# Humanoid_Robotic_Hand.net
KiCad netlist of a schematic drawn in Altium Designer
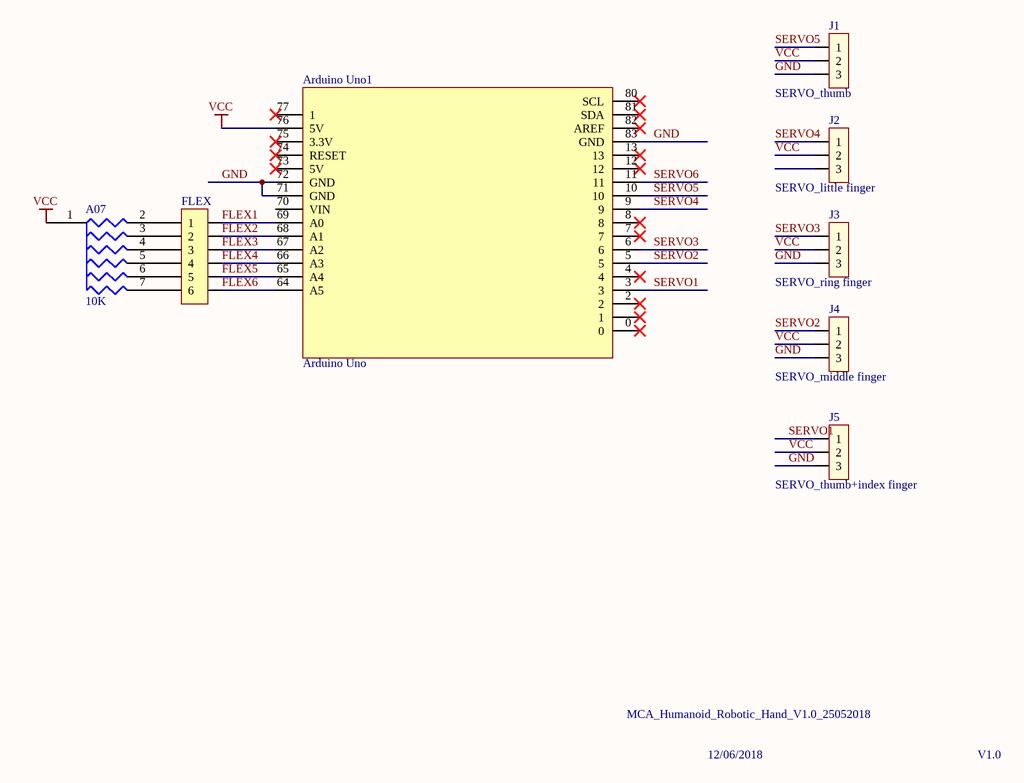
[diagram p0: Humanoid_Robotic_Hand.SchDoc]

(export (version "E")
  (design (tool "Eeschema 10.0.6"))
  (components
    (comp (ref "A07")
      (value "10K")
      (footprint "RES PACK A07")
      (libsource (lib "MH_Thu Vien Du An") (part "Res Pack A07"))
    )
    (comp (ref "Arduino Uno1")
      (value "Arduino Uno")
      (footprint "Arduino Uno")
      (fields (field (name "PUBLISHER") "Altium Limited"))
      (libsource (lib "NamTEch_Lib") (part "Arduino Uno"))
    )
    (comp (ref "FLEX")
      (value "~")
      (footprint "JUMPER 6X2")
      (description "Jump 6x2P 2.54")
      (libsource (lib "NamTEch_Lib") (part "Jump 6x2_MH"))
    )
    (comp (ref "J1")
      (value "SERVO_thumb")
      (footprint "JP3")
      (description "Jumper 3")
      (libsource (lib "MH_Thu Vien Du An") (part "JP3"))
    )
    (comp (ref "J2")
      (value "SERVO_little finger")
      (footprint "JP3")
      (description "Jumper 3")
      (libsource (lib "MH_Thu Vien Du An") (part "JP3"))
    )
    (comp (ref "J3")
      (value "SERVO_ring finger")
      (footprint "JP3")
      (description "Jumper 3")
      (libsource (lib "MH_Thu Vien Du An") (part "JP3"))
    )
    (comp (ref "J4")
      (value "SERVO_middle finger")
      (footprint "JP3")
      (description "Jumper 3")
      (libsource (lib "MH_Thu Vien Du An") (part "JP3"))
    )
    (comp (ref "J5")
      (value "SERVO_thumb+index finger")
      (footprint "JP3")
      (description "Jumper 3")
      (libsource (lib "MH_Thu Vien Du An") (part "JP3"))
    )
  )
  (nets
    (net (code "1") (name "/FLEX1") (class "Default")
      (node (ref "Arduino Uno1") (pin "69") (pinfunction "A0_69") (pintype "passive"))
      (node (ref "FLEX") (pin "7") (pinfunction "7_7") (pintype "passive"))
    )
    (net (code "2") (name "/FLEX2") (class "Default")
      (node (ref "Arduino Uno1") (pin "68") (pinfunction "A1_68") (pintype "passive"))
      (node (ref "FLEX") (pin "8") (pinfunction "8_8") (pintype "passive"))
    )
    (net (code "3") (name "/FLEX3") (class "Default")
      (node (ref "Arduino Uno1") (pin "67") (pinfunction "A2_67") (pintype "passive"))
      (node (ref "FLEX") (pin "9") (pinfunction "9_9") (pintype "passive"))
    )
    (net (code "4") (name "/FLEX4") (class "Default")
      (node (ref "Arduino Uno1") (pin "66") (pinfunction "A3_66") (pintype "passive"))
      (node (ref "FLEX") (pin "10") (pinfunction "10_10") (pintype "passive"))
    )
    (net (code "5") (name "/FLEX5") (class "Default")
      (node (ref "Arduino Uno1") (pin "65") (pinfunction "A4_65") (pintype "passive"))
      (node (ref "FLEX") (pin "11") (pinfunction "11_11") (pintype "passive"))
    )
    (net (code "6") (name "/FLEX6") (class "Default")
      (node (ref "Arduino Uno1") (pin "64") (pinfunction "A5_64") (pintype "passive"))
      (node (ref "FLEX") (pin "12") (pinfunction "12_12") (pintype "passive"))
    )
    (net (code "7") (name "/GND") (class "Default")
      (node (ref "Arduino Uno1") (pin "71") (pinfunction "GND_71") (pintype "passive"))
      (node (ref "Arduino Uno1") (pin "72") (pinfunction "GND_72") (pintype "passive"))
      (node (ref "Arduino Uno1") (pin "83") (pinfunction "GND_83") (pintype "passive"))
      (node (ref "J1") (pin "3") (pinfunction "3_3") (pintype "passive"))
      (node (ref "J3") (pin "3") (pinfunction "3_3") (pintype "passive"))
      (node (ref "J4") (pin "3") (pinfunction "3_3") (pintype "passive"))
      (node (ref "J5") (pin "3") (pinfunction "3_3") (pintype "passive"))
    )
    (net (code "8") (name "/SERVO1") (class "Default")
      (node (ref "Arduino Uno1") (pin "3") (pinfunction "3_3") (pintype "passive"))
      (node (ref "J5") (pin "1") (pinfunction "1_1") (pintype "passive"))
    )
    (net (code "9") (name "/SERVO2") (class "Default")
      (node (ref "Arduino Uno1") (pin "5") (pinfunction "5_5") (pintype "passive"))
      (node (ref "J4") (pin "1") (pinfunction "1_1") (pintype "passive"))
    )
    (net (code "10") (name "/SERVO3") (class "Default")
      (node (ref "Arduino Uno1") (pin "6") (pinfunction "6_6") (pintype "passive"))
      (node (ref "J3") (pin "1") (pinfunction "1_1") (pintype "passive"))
    )
    (net (code "11") (name "/SERVO4") (class "Default")
      (node (ref "Arduino Uno1") (pin "9") (pinfunction "9_9") (pintype "passive"))
      (node (ref "J2") (pin "1") (pinfunction "1_1") (pintype "passive"))
    )
    (net (code "12") (name "/SERVO5") (class "Default")
      (node (ref "Arduino Uno1") (pin "10") (pinfunction "10_10") (pintype "passive"))
      (node (ref "J1") (pin "1") (pinfunction "1_1") (pintype "passive"))
    )
    (net (code "13") (name "/SERVO6") (class "Default")
      (node (ref "Arduino Uno1") (pin "11") (pinfunction "11_11") (pintype "passive"))
    )
    (net (code "14") (name "Net-(A07-Pad2)") (class "Default")
      (node (ref "A07") (pin "2") (pinfunction "2_2") (pintype "passive"))
      (node (ref "FLEX") (pin "1") (pinfunction "1_1") (pintype "passive"))
    )
    (net (code "15") (name "Net-(A07-Pad3)") (class "Default")
      (node (ref "A07") (pin "3") (pinfunction "3_3") (pintype "passive"))
      (node (ref "FLEX") (pin "2") (pinfunction "2_2") (pintype "passive"))
    )
    (net (code "16") (name "Net-(A07-Pad4)") (class "Default")
      (node (ref "A07") (pin "4") (pinfunction "4_4") (pintype "passive"))
      (node (ref "FLEX") (pin "3") (pinfunction "3_3") (pintype "passive"))
    )
    (net (code "17") (name "Net-(A07-Pad5)") (class "Default")
      (node (ref "A07") (pin "5") (pinfunction "5_5") (pintype "passive"))
      (node (ref "FLEX") (pin "4") (pinfunction "4_4") (pintype "passive"))
    )
    (net (code "18") (name "Net-(A07-Pad6)") (class "Default")
      (node (ref "A07") (pin "6") (pinfunction "6_6") (pintype "passive"))
      (node (ref "FLEX") (pin "5") (pinfunction "5_5") (pintype "passive"))
    )
    (net (code "19") (name "Net-(A07-Pad7)") (class "Default")
      (node (ref "A07") (pin "7") (pinfunction "7_7") (pintype "passive"))
      (node (ref "FLEX") (pin "6") (pinfunction "6_6") (pintype "passive"))
    )
    (net (code "20") (name "VCC") (class "Default")
      (node (ref "A07") (pin "1") (pinfunction "1_1") (pintype "passive"))
      (node (ref "Arduino Uno1") (pin "76") (pinfunction "5V_76") (pintype "passive"))
      (node (ref "J1") (pin "2") (pinfunction "2_2") (pintype "passive"))
      (node (ref "J2") (pin "2") (pinfunction "2_2") (pintype "passive"))
      (node (ref "J3") (pin "2") (pinfunction "2_2") (pintype "passive"))
      (node (ref "J4") (pin "2") (pinfunction "2_2") (pintype "passive"))
      (node (ref "J5") (pin "2") (pinfunction "2_2") (pintype "passive"))
    )
    (net (code "21") (name "unconnected-(Arduino Uno1-1-Pad77)") (class "Default")
      (node (ref "Arduino Uno1") (pin "77") (pinfunction "1_77") (pintype "passive+no_connect"))
    )
    (net (code "22") (name "unconnected-(Arduino Uno1-3.3V-Pad75)") (class "Default")
      (node (ref "Arduino Uno1") (pin "75") (pinfunction "3.3V_75") (pintype "passive+no_connect"))
    )
    (net (code "23") (name "unconnected-(Arduino Uno1-5V-Pad73)") (class "Default")
      (node (ref "Arduino Uno1") (pin "73") (pinfunction "5V_73") (pintype "passive+no_connect"))
    )
    (net (code "24") (name "unconnected-(Arduino Uno1-AREF-Pad82)") (class "Default")
      (node (ref "Arduino Uno1") (pin "82") (pinfunction "AREF_82") (pintype "passive+no_connect"))
    )
    (net (code "25") (name "unconnected-(Arduino Uno1-Pad0)") (class "Default")
      (node (ref "Arduino Uno1") (pin "0") (pinfunction "0_0") (pintype "passive+no_connect"))
    )
    (net (code "26") (name "unconnected-(Arduino Uno1-Pad1)") (class "Default")
      (node (ref "Arduino Uno1") (pin "1") (pinfunction "1_1") (pintype "passive+no_connect"))
    )
    (net (code "27") (name "unconnected-(Arduino Uno1-Pad2)") (class "Default")
      (node (ref "Arduino Uno1") (pin "2") (pinfunction "2_2") (pintype "passive+no_connect"))
    )
    (net (code "28") (name "unconnected-(Arduino Uno1-Pad4)") (class "Default")
      (node (ref "Arduino Uno1") (pin "4") (pinfunction "4_4") (pintype "passive+no_connect"))
    )
    (net (code "29") (name "unconnected-(Arduino Uno1-Pad7)") (class "Default")
      (node (ref "Arduino Uno1") (pin "7") (pinfunction "7_7") (pintype "passive+no_connect"))
    )
    (net (code "30") (name "unconnected-(Arduino Uno1-Pad8)") (class "Default")
      (node (ref "Arduino Uno1") (pin "8") (pinfunction "8_8") (pintype "passive+no_connect"))
    )
    (net (code "31") (name "unconnected-(Arduino Uno1-Pad12)") (class "Default")
      (node (ref "Arduino Uno1") (pin "12") (pinfunction "12_12") (pintype "passive+no_connect"))
    )
    (net (code "32") (name "unconnected-(Arduino Uno1-Pad13)") (class "Default")
      (node (ref "Arduino Uno1") (pin "13") (pinfunction "13_13") (pintype "passive+no_connect"))
    )
    (net (code "33") (name "unconnected-(Arduino Uno1-RESET-Pad74)") (class "Default")
      (node (ref "Arduino Uno1") (pin "74") (pinfunction "RESET_74") (pintype "passive+no_connect"))
    )
    (net (code "34") (name "unconnected-(Arduino Uno1-SCL-Pad80)") (class "Default")
      (node (ref "Arduino Uno1") (pin "80") (pinfunction "SCL_80") (pintype "passive+no_connect"))
    )
    (net (code "35") (name "unconnected-(Arduino Uno1-SDA-Pad81)") (class "Default")
      (node (ref "Arduino Uno1") (pin "81") (pinfunction "SDA_81") (pintype "passive+no_connect"))
    )
    (net (code "36") (name "unconnected-(Arduino Uno1-VIN-Pad70)") (class "Default")
      (node (ref "Arduino Uno1") (pin "70") (pinfunction "VIN_70") (pintype "passive"))
    )
    (net (code "37") (name "unconnected-(J2-Pad3)") (class "Default")
      (node (ref "J2") (pin "3") (pinfunction "3_3") (pintype "passive"))
    )
  )
)
